# design.net
KiCad netlist of a schematic drawn in EasyEDA Pro
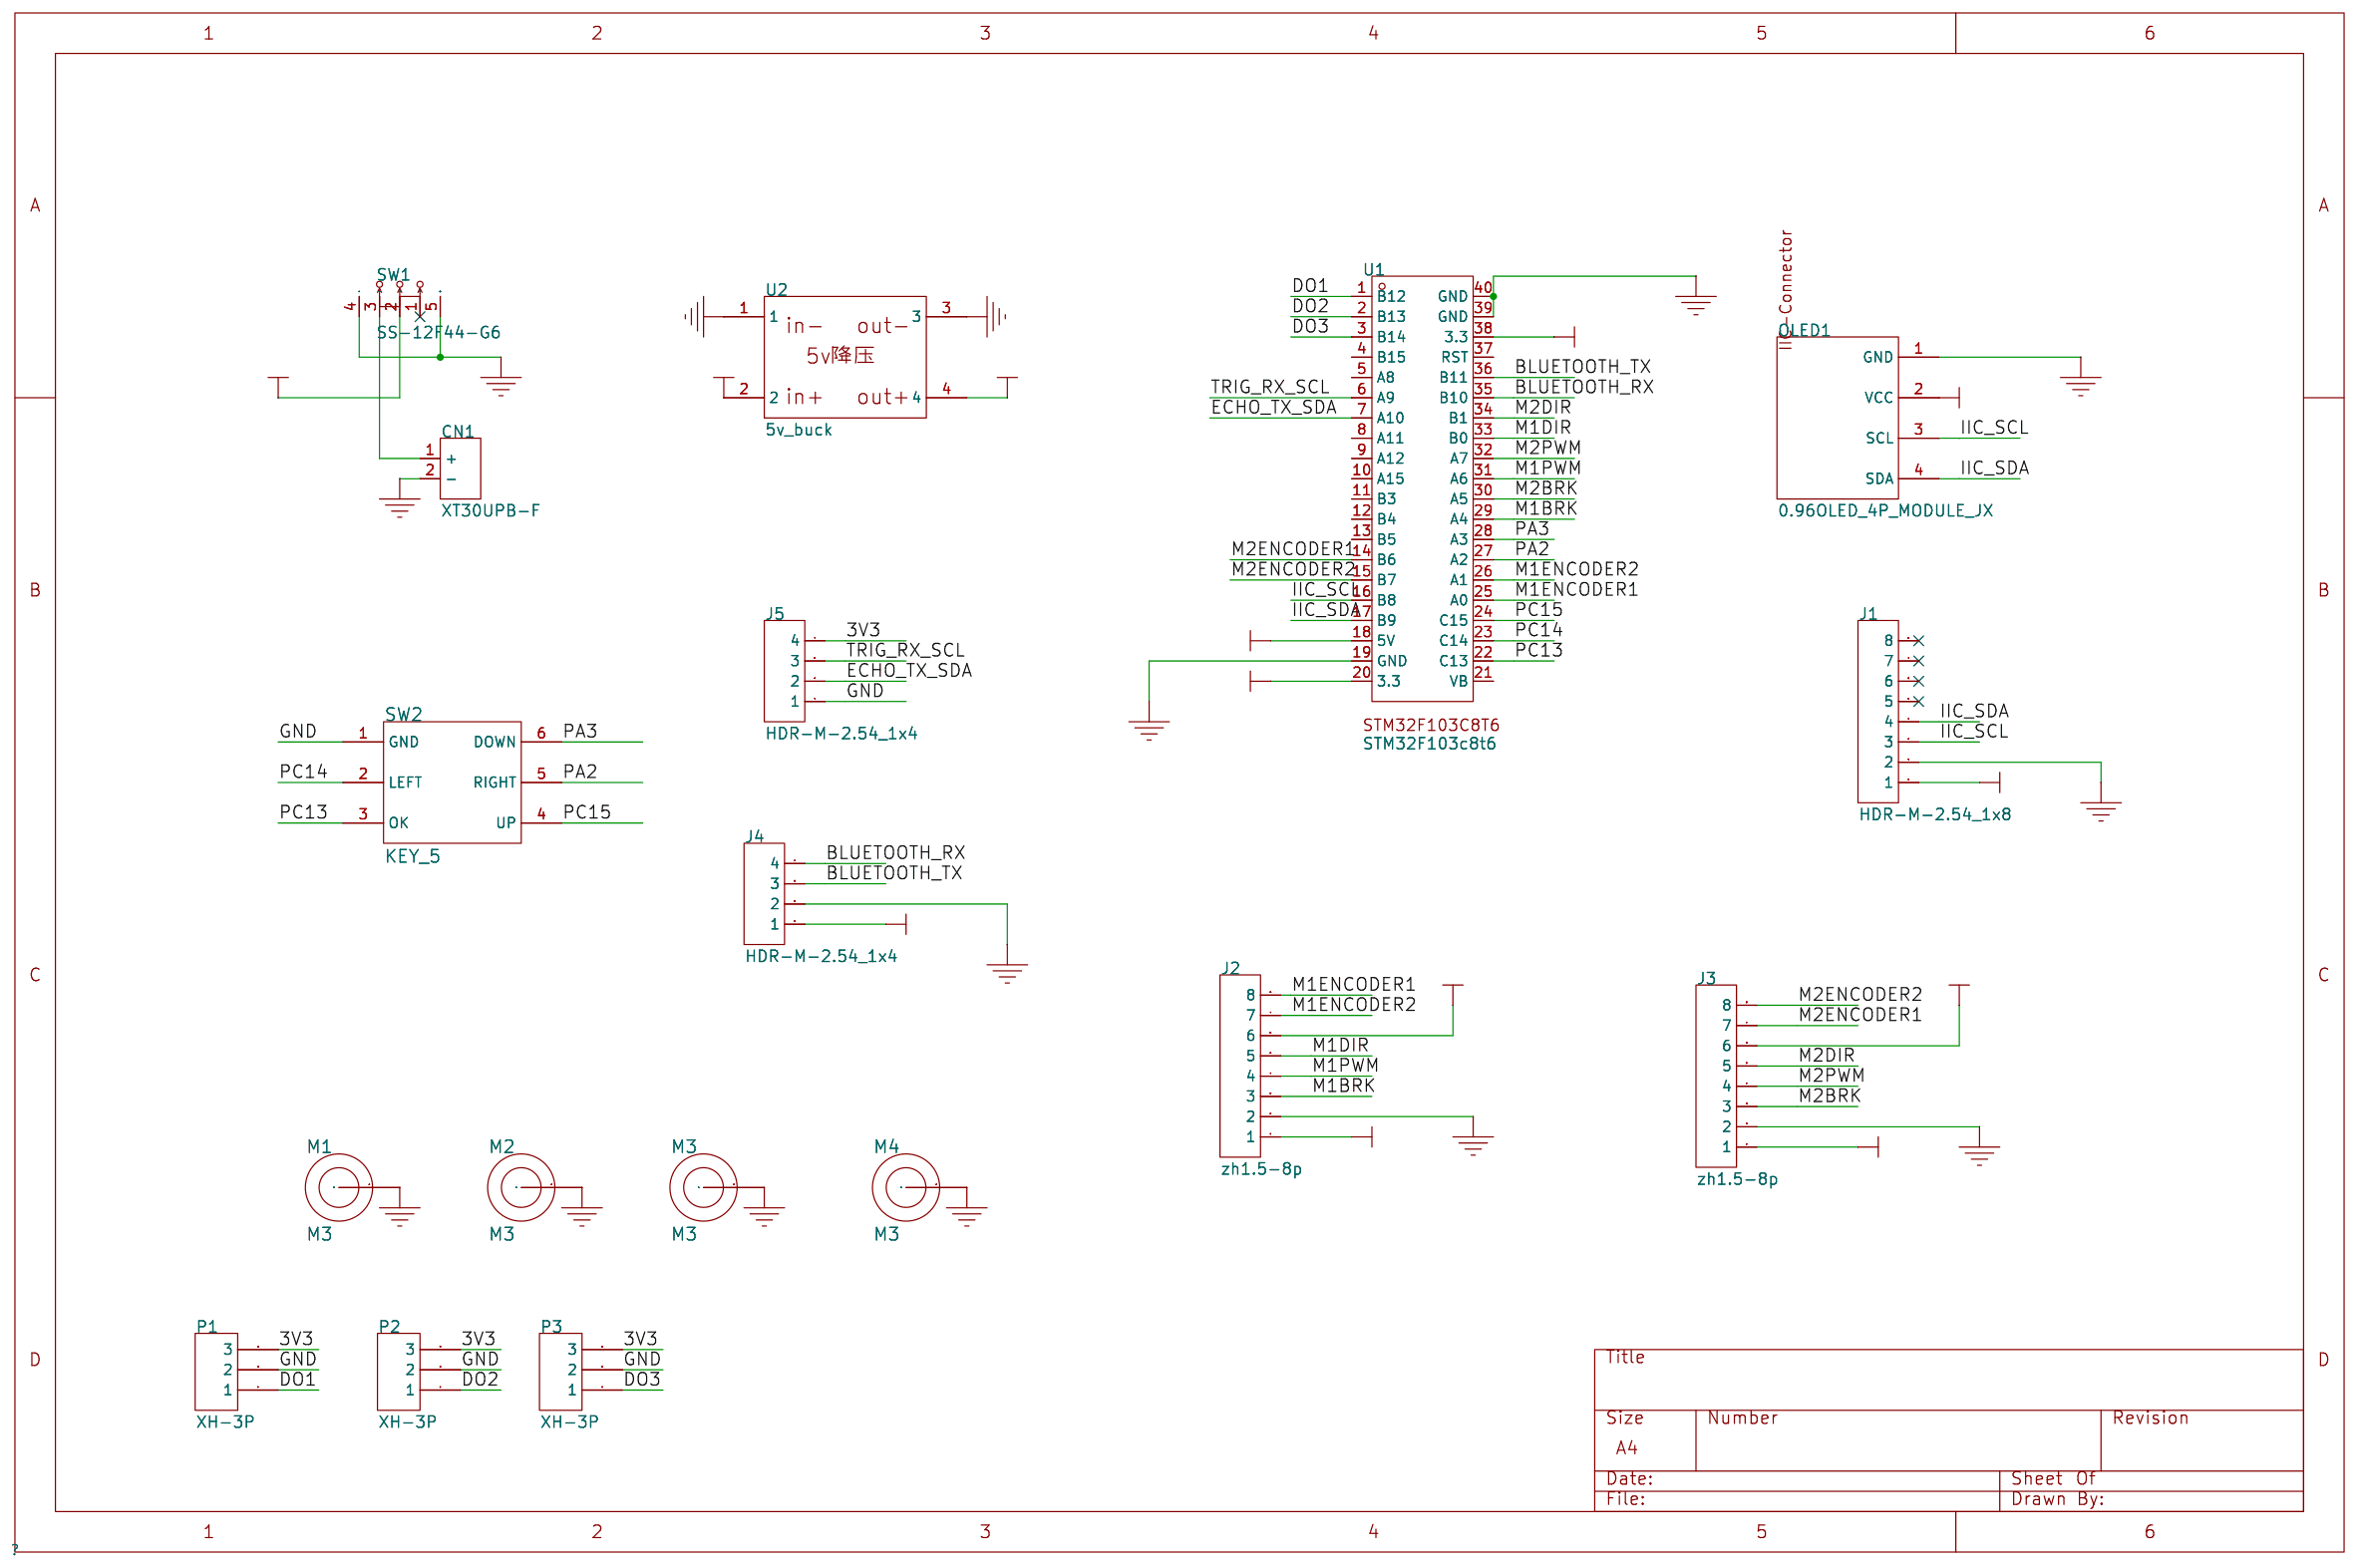
[diagram p0: schematic sheet]

(export (version "E")
  (design (tool "Eeschema 10.0.6"))
  (components
    (comp (ref "CN1")
      (value "XT30UPB-F")
      (footprint "easyedapro:XT30")
      (libsource (lib "easyedapro") (part "XT30"))
    )
    (comp (ref "J1")
      (value "HDR-M-2.54_1x8")
      (footprint "easyedapro:HDR-M-2.54_1X8")
      (libsource (lib "easyedapro") (part "HDR-M-2.54_1x8"))
    )
    (comp (ref "J2")
      (value "zh1.5-8p")
      (footprint "easyedapro:ZH1.5-8P")
      (libsource (lib "easyedapro") (part "zh1.5-8p"))
    )
    (comp (ref "J3")
      (value "zh1.5-8p")
      (footprint "easyedapro:ZH1.5-8P")
      (libsource (lib "easyedapro") (part "zh1.5-8p"))
    )
    (comp (ref "J4")
      (value "HDR-M-2.54_1x4")
      (footprint "easyedapro:HDR-M-2.54_1X4")
      (libsource (lib "easyedapro") (part "HDR-M-2.54_1x4"))
    )
    (comp (ref "J5")
      (value "HDR-M-2.54_1x4")
      (footprint "easyedapro:HDR-M-2.54_1X4")
      (libsource (lib "easyedapro") (part "HDR-M-2.54_1x4"))
    )
    (comp (ref "M1") (value "M3") (footprint "easyedapro:M3") (libsource (lib "easyedapro") (part "M3")))
    (comp (ref "M2") (value "M3") (footprint "easyedapro:M3") (libsource (lib "easyedapro") (part "M3")))
    (comp (ref "M3") (value "M3") (footprint "easyedapro:M3") (libsource (lib "easyedapro") (part "M3")))
    (comp (ref "M4") (value "M3") (footprint "easyedapro:M3") (libsource (lib "easyedapro") (part "M3")))
    (comp (ref "OLED1")
      (value "0.96OLED_4P_MODULE_JX")
      (footprint "easyedapro:0.96OLED_4P")
      (libsource (lib "easyedapro") (part "0.96OLED_4P_MODULE_JX"))
    )
    (comp (ref "P1")
      (value "XH-3P")
      (footprint "easyedapro:XH3pin")
      (libsource (lib "easyedapro") (part "XH-3P"))
    )
    (comp (ref "P2")
      (value "XH-3P")
      (footprint "easyedapro:XH3pin")
      (libsource (lib "easyedapro") (part "XH-3P"))
    )
    (comp (ref "P3")
      (value "XH-3P")
      (footprint "easyedapro:XH3pin")
      (libsource (lib "easyedapro") (part "XH-3P"))
    )
    (comp (ref "SW1")
      (value "SS-12F44-G6")
      (footprint "easyedapro:SW-TH_SS-12F44-GX")
      (fields (field (name "Manufacturer") "USAKRO"))
      (libsource (lib "easyedapro") (part "SS-12F44-G6"))
    )
    (comp (ref "SW2")
      (value "KEY_5")
      (footprint "easyedapro:KEY_5")
      (description "五向导航按钮")
      (libsource (lib "easyedapro") (part "KEY_5"))
    )
    (comp (ref "U1")
      (value "STM32F103c8t6")
      (footprint "easyedapro:stm32f103coreboard")
      (libsource (lib "easyedapro") (part "STM32F103c8t6"))
    )
    (comp (ref "U2")
      (value "5v_buck")
      (footprint "easyedapro:5V_BUCK")
      (libsource (lib "easyedapro") (part "5v_buck"))
    )
  )
  (nets
    (net (code "1") (name "/BLUETOOTH_RX") (class "Default")
      (node (ref "J4") (pin "4") (pinfunction "4_4") (pintype "input"))
      (node (ref "U1") (pin "35") (pinfunction "B10_35") (pintype "input"))
    )
    (net (code "2") (name "/BLUETOOTH_TX") (class "Default")
      (node (ref "J4") (pin "3") (pinfunction "3_3") (pintype "input"))
      (node (ref "U1") (pin "36") (pinfunction "B11_36") (pintype "input"))
    )
    (net (code "3") (name "/DO1") (class "Default")
      (node (ref "P1") (pin "1") (pinfunction "1_1") (pintype "input"))
      (node (ref "U1") (pin "1") (pinfunction "B12_1") (pintype "input"))
    )
    (net (code "4") (name "/DO2") (class "Default")
      (node (ref "P2") (pin "1") (pinfunction "1_1") (pintype "input"))
      (node (ref "U1") (pin "2") (pinfunction "B13_2") (pintype "input"))
    )
    (net (code "5") (name "/DO3") (class "Default")
      (node (ref "P3") (pin "1") (pinfunction "1_1") (pintype "input"))
      (node (ref "U1") (pin "3") (pinfunction "B14_3") (pintype "input"))
    )
    (net (code "6") (name "/ECHO_TX_SDA") (class "Default")
      (node (ref "J5") (pin "2") (pinfunction "2_2") (pintype "input"))
      (node (ref "U1") (pin "7") (pinfunction "A10_7") (pintype "input"))
    )
    (net (code "7") (name "/IIC_SCL") (class "Default")
      (node (ref "J1") (pin "3") (pinfunction "3_3") (pintype "input"))
      (node (ref "OLED1") (pin "3") (pinfunction "SCL_3") (pintype "input"))
      (node (ref "U1") (pin "16") (pinfunction "B8_16") (pintype "input"))
    )
    (net (code "8") (name "/IIC_SDA") (class "Default")
      (node (ref "J1") (pin "4") (pinfunction "4_4") (pintype "input"))
      (node (ref "OLED1") (pin "4") (pinfunction "SDA_4") (pintype "input"))
      (node (ref "U1") (pin "17") (pinfunction "B9_17") (pintype "input"))
    )
    (net (code "9") (name "/M1BRK") (class "Default")
      (node (ref "J2") (pin "3") (pinfunction "3_3") (pintype "input"))
      (node (ref "U1") (pin "29") (pinfunction "A4_29") (pintype "input"))
    )
    (net (code "10") (name "/M1DIR") (class "Default")
      (node (ref "J2") (pin "5") (pinfunction "5_5") (pintype "input"))
      (node (ref "U1") (pin "33") (pinfunction "B0_33") (pintype "input"))
    )
    (net (code "11") (name "/M1ENCODER1") (class "Default")
      (node (ref "J2") (pin "8") (pinfunction "8_8") (pintype "input"))
      (node (ref "U1") (pin "25") (pinfunction "A0_25") (pintype "input"))
    )
    (net (code "12") (name "/M1ENCODER2") (class "Default")
      (node (ref "J2") (pin "7") (pinfunction "7_7") (pintype "input"))
      (node (ref "U1") (pin "26") (pinfunction "A1_26") (pintype "input"))
    )
    (net (code "13") (name "/M1PWM") (class "Default")
      (node (ref "J2") (pin "4") (pinfunction "4_4") (pintype "input"))
      (node (ref "U1") (pin "31") (pinfunction "A6_31") (pintype "input"))
    )
    (net (code "14") (name "/M2BRK") (class "Default")
      (node (ref "J3") (pin "3") (pinfunction "3_3") (pintype "input"))
      (node (ref "U1") (pin "30") (pinfunction "A5_30") (pintype "input"))
    )
    (net (code "15") (name "/M2DIR") (class "Default")
      (node (ref "J3") (pin "5") (pinfunction "5_5") (pintype "input"))
      (node (ref "U1") (pin "34") (pinfunction "B1_34") (pintype "input"))
    )
    (net (code "16") (name "/M2ENCODER1") (class "Default")
      (node (ref "J3") (pin "7") (pinfunction "7_7") (pintype "input"))
      (node (ref "U1") (pin "14") (pinfunction "B6_14") (pintype "input"))
    )
    (net (code "17") (name "/M2ENCODER2") (class "Default")
      (node (ref "J3") (pin "8") (pinfunction "8_8") (pintype "input"))
      (node (ref "U1") (pin "15") (pinfunction "B7_15") (pintype "input"))
    )
    (net (code "18") (name "/M2PWM") (class "Default")
      (node (ref "J3") (pin "4") (pinfunction "4_4") (pintype "input"))
      (node (ref "U1") (pin "32") (pinfunction "A7_32") (pintype "input"))
    )
    (net (code "19") (name "/PA2") (class "Default")
      (node (ref "SW2") (pin "5") (pinfunction "RIGHT_5") (pintype "input"))
      (node (ref "U1") (pin "27") (pinfunction "A2_27") (pintype "input"))
    )
    (net (code "20") (name "/PA3") (class "Default")
      (node (ref "SW2") (pin "6") (pinfunction "DOWN_6") (pintype "input"))
      (node (ref "U1") (pin "28") (pinfunction "A3_28") (pintype "input"))
    )
    (net (code "21") (name "/PC13") (class "Default")
      (node (ref "SW2") (pin "3") (pinfunction "OK_3") (pintype "input"))
      (node (ref "U1") (pin "22") (pinfunction "C13_22") (pintype "input"))
    )
    (net (code "22") (name "/PC14") (class "Default")
      (node (ref "SW2") (pin "2") (pinfunction "LEFT_2") (pintype "input"))
      (node (ref "U1") (pin "23") (pinfunction "C14_23") (pintype "input"))
    )
    (net (code "23") (name "/PC15") (class "Default")
      (node (ref "SW2") (pin "4") (pinfunction "UP_4") (pintype "input"))
      (node (ref "U1") (pin "24") (pinfunction "C15_24") (pintype "input"))
    )
    (net (code "24") (name "/TRIG_RX_SCL") (class "Default")
      (node (ref "J5") (pin "3") (pinfunction "3_3") (pintype "input"))
      (node (ref "U1") (pin "6") (pinfunction "A9_6") (pintype "input"))
    )
    (net (code "25") (name "3V3") (class "Default")
      (node (ref "J1") (pin "1") (pinfunction "1_1") (pintype "input"))
      (node (ref "J2") (pin "6") (pinfunction "6_6") (pintype "input"))
      (node (ref "J3") (pin "6") (pinfunction "6_6") (pintype "input"))
      (node (ref "J5") (pin "4") (pinfunction "4_4") (pintype "input"))
      (node (ref "OLED1") (pin "2") (pinfunction "VCC_2") (pintype "input"))
      (node (ref "P1") (pin "3") (pinfunction "3_3") (pintype "input"))
      (node (ref "P2") (pin "3") (pinfunction "3_3") (pintype "input"))
      (node (ref "P3") (pin "3") (pinfunction "3_3") (pintype "input"))
      (node (ref "U1") (pin "20") (pinfunction "3.3_20") (pintype "input"))
      (node (ref "U1") (pin "38") (pinfunction "3.3_38") (pintype "input"))
    )
    (net (code "26") (name "5V") (class "Default")
      (node (ref "J4") (pin "1") (pinfunction "1_1") (pintype "input"))
      (node (ref "U1") (pin "18") (pinfunction "5V_18") (pintype "input"))
      (node (ref "U2") (pin "4") (pinfunction "4_4") (pintype "input"))
    )
    (net (code "27") (name "GND") (class "Default")
      (node (ref "CN1") (pin "2") (pinfunction "-_2") (pintype "input"))
      (node (ref "J1") (pin "2") (pinfunction "2_2") (pintype "input"))
      (node (ref "J2") (pin "2") (pinfunction "2_2") (pintype "input"))
      (node (ref "J3") (pin "2") (pinfunction "2_2") (pintype "input"))
      (node (ref "J4") (pin "2") (pinfunction "2_2") (pintype "input"))
      (node (ref "J5") (pin "1") (pinfunction "1_1") (pintype "input"))
      (node (ref "M1") (pin "1") (pinfunction "1_1") (pintype "input"))
      (node (ref "M2") (pin "1") (pinfunction "1_1") (pintype "input"))
      (node (ref "M3") (pin "1") (pinfunction "1_1") (pintype "input"))
      (node (ref "M4") (pin "1") (pinfunction "1_1") (pintype "input"))
      (node (ref "OLED1") (pin "1") (pinfunction "GND_1") (pintype "input"))
      (node (ref "P1") (pin "2") (pinfunction "2_2") (pintype "input"))
      (node (ref "P2") (pin "2") (pinfunction "2_2") (pintype "input"))
      (node (ref "P3") (pin "2") (pinfunction "2_2") (pintype "input"))
      (node (ref "SW1") (pin "4") (pinfunction "4_4") (pintype "input"))
      (node (ref "SW1") (pin "5") (pinfunction "5_5") (pintype "input"))
      (node (ref "SW2") (pin "1") (pinfunction "GND_1") (pintype "input"))
      (node (ref "U1") (pin "19") (pinfunction "GND_19") (pintype "input"))
      (node (ref "U1") (pin "39") (pinfunction "GND_39") (pintype "input"))
      (node (ref "U1") (pin "40") (pinfunction "GND_40") (pintype "input"))
      (node (ref "U2") (pin "1") (pinfunction "1_1") (pintype "input"))
      (node (ref "U2") (pin "3") (pinfunction "3_3") (pintype "input"))
    )
    (net (code "28") (name "Net-(CN1-+)") (class "Default")
      (node (ref "CN1") (pin "1") (pinfunction "+_1") (pintype "input"))
      (node (ref "SW1") (pin "3") (pinfunction "3_3") (pintype "input"))
    )
    (net (code "29") (name "VBAT") (class "Default")
      (node (ref "J2") (pin "1") (pinfunction "1_1") (pintype "input"))
      (node (ref "J3") (pin "1") (pinfunction "1_1") (pintype "input"))
      (node (ref "SW1") (pin "2") (pinfunction "2_2") (pintype "input"))
      (node (ref "U2") (pin "2") (pinfunction "2_2") (pintype "input"))
    )
    (net (code "30") (name "unconnected-(J1-Pad5)") (class "Default")
      (node (ref "J1") (pin "5") (pinfunction "5_5") (pintype "input+no_connect"))
    )
    (net (code "31") (name "unconnected-(J1-Pad6)") (class "Default")
      (node (ref "J1") (pin "6") (pinfunction "6_6") (pintype "input+no_connect"))
    )
    (net (code "32") (name "unconnected-(J1-Pad7)") (class "Default")
      (node (ref "J1") (pin "7") (pinfunction "7_7") (pintype "input+no_connect"))
    )
    (net (code "33") (name "unconnected-(J1-Pad8)") (class "Default")
      (node (ref "J1") (pin "8") (pinfunction "8_8") (pintype "input+no_connect"))
    )
    (net (code "34") (name "unconnected-(SW1-Pad1)") (class "Default")
      (node (ref "SW1") (pin "1") (pinfunction "1_1") (pintype "input+no_connect"))
    )
    (net (code "35") (name "unconnected-(U1-A8-Pad5)") (class "Default")
      (node (ref "U1") (pin "5") (pinfunction "A8_5") (pintype "input"))
    )
    (net (code "36") (name "unconnected-(U1-A11-Pad8)") (class "Default")
      (node (ref "U1") (pin "8") (pinfunction "A11_8") (pintype "input"))
    )
    (net (code "37") (name "unconnected-(U1-A12-Pad9)") (class "Default")
      (node (ref "U1") (pin "9") (pinfunction "A12_9") (pintype "input"))
    )
    (net (code "38") (name "unconnected-(U1-A15-Pad10)") (class "Default")
      (node (ref "U1") (pin "10") (pinfunction "A15_10") (pintype "input"))
    )
    (net (code "39") (name "unconnected-(U1-B3-Pad11)") (class "Default")
      (node (ref "U1") (pin "11") (pinfunction "B3_11") (pintype "input"))
    )
    (net (code "40") (name "unconnected-(U1-B4-Pad12)") (class "Default")
      (node (ref "U1") (pin "12") (pinfunction "B4_12") (pintype "input"))
    )
    (net (code "41") (name "unconnected-(U1-B5-Pad13)") (class "Default")
      (node (ref "U1") (pin "13") (pinfunction "B5_13") (pintype "input"))
    )
    (net (code "42") (name "unconnected-(U1-B15-Pad4)") (class "Default")
      (node (ref "U1") (pin "4") (pinfunction "B15_4") (pintype "input"))
    )
    (net (code "43") (name "unconnected-(U1-RST-Pad37)") (class "Default")
      (node (ref "U1") (pin "37") (pinfunction "RST_37") (pintype "input"))
    )
    (net (code "44") (name "unconnected-(U1-VB-Pad21)") (class "Default")
      (node (ref "U1") (pin "21") (pinfunction "VB_21") (pintype "input"))
    )
  )
)
